# RHD2132_headstage1.net
KiCad netlist of a schematic drawn in Altium Designer
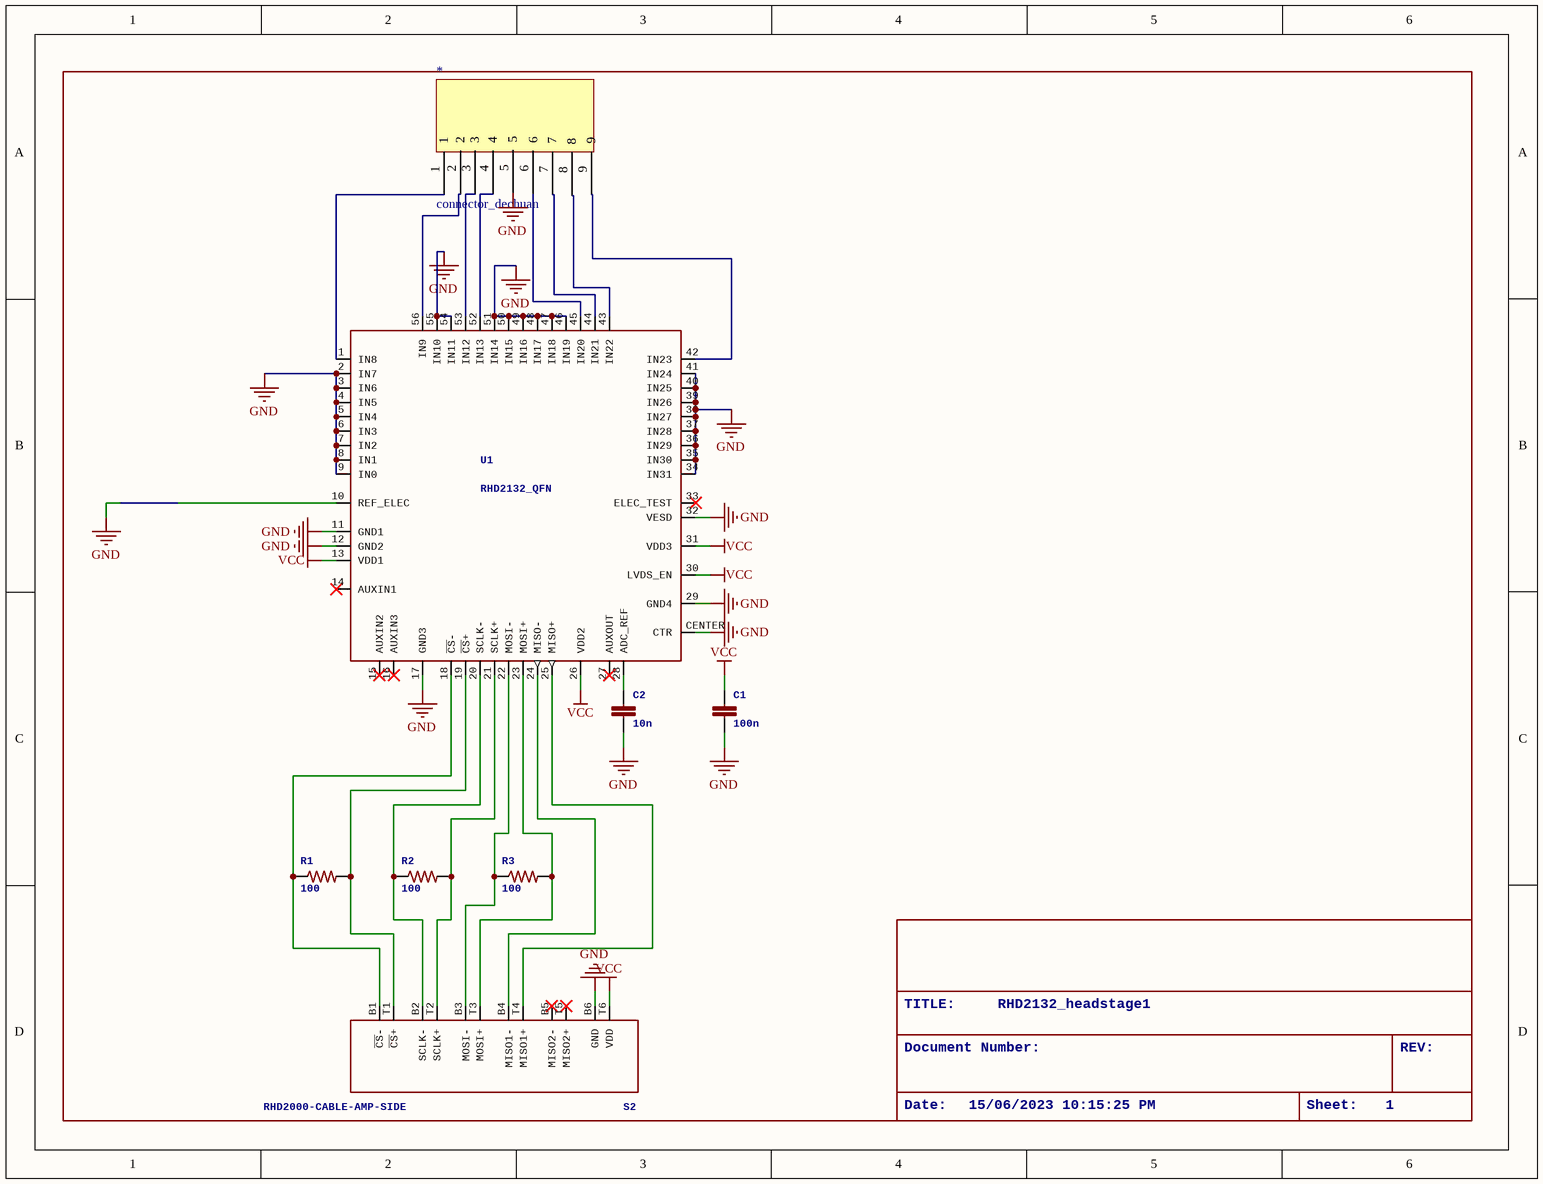
[diagram p0: RHD2132_headstage1.SchDoc]

(export (version "E")
  (design (tool "Eeschema 10.0.6"))
  (components
    (comp (ref "*")
      (value "connector_dechuan")
      (footprint "connector_dechuan")
      (libsource (lib "Schlib1") (part "connector_dechuan"))
    )
    (comp (ref "C1")
      (value "100n")
      (footprint "0402")
      (description "Capacitor")
      (libsource (lib "RHD2000_eval_board") (part "C_0402"))
    )
    (comp (ref "C2")
      (value "10n")
      (footprint "0402")
      (description "Capacitor")
      (libsource (lib "RHD2000_eval_board") (part "C_0402"))
    )
    (comp (ref "R1")
      (value "100")
      (footprint "0402")
      (description "Resistor")
      (libsource (lib "RHD2000_eval_board") (part "R_0402"))
    )
    (comp (ref "R2")
      (value "100")
      (footprint "0402")
      (description "Resistor")
      (libsource (lib "RHD2000_eval_board") (part "R_0402"))
    )
    (comp (ref "R3")
      (value "100")
      (footprint "0402")
      (description "Resistor")
      (libsource (lib "RHD2000_eval_board") (part "R_0402"))
    )
    (comp (ref "S2")
      (value "RHD2000-CABLE-AMP-SIDE")
      (footprint "OMNETICS_PZN-12-AA")
      (libsource (lib "RHD2000") (part "RHD2000-CABLE-AMP-SIDE"))
    )
    (comp (ref "U1")
      (value "RHD2132_QFN")
      (footprint "QFN56_8_X_8_LARGE")
      (libsource (lib "RHD2000") (part "RHD2132_QFN"))
    )
  )
  (nets
    (net (code "1") (name "GND") (class "Default")
      (node (ref "*") (pin "5") (pinfunction "5_5") (pintype "passive"))
      (node (ref "C1") (pin "2") (pinfunction "2_2") (pintype "passive"))
      (node (ref "C2") (pin "2") (pinfunction "2_2") (pintype "passive"))
      (node (ref "S2") (pin "B6") (pinfunction "GND_B6") (pintype "power_in"))
      (node (ref "U1") (pin "10") (pinfunction "REF_ELEC_10") (pintype "passive"))
      (node (ref "U1") (pin "11") (pinfunction "GND1_11") (pintype "power_in"))
      (node (ref "U1") (pin "12") (pinfunction "GND2_12") (pintype "power_in"))
      (node (ref "U1") (pin "17") (pinfunction "GND3_17") (pintype "power_in"))
      (node (ref "U1") (pin "2") (pinfunction "IN7_2") (pintype "passive"))
      (node (ref "U1") (pin "29") (pinfunction "GND4_29") (pintype "power_in"))
      (node (ref "U1") (pin "3") (pinfunction "IN6_3") (pintype "passive"))
      (node (ref "U1") (pin "32") (pinfunction "VESD_32") (pintype "power_in"))
      (node (ref "U1") (pin "34") (pinfunction "IN31_34") (pintype "passive"))
      (node (ref "U1") (pin "35") (pinfunction "IN30_35") (pintype "passive"))
      (node (ref "U1") (pin "36") (pinfunction "IN29_36") (pintype "passive"))
      (node (ref "U1") (pin "37") (pinfunction "IN28_37") (pintype "passive"))
      (node (ref "U1") (pin "38") (pinfunction "IN27_38") (pintype "passive"))
      (node (ref "U1") (pin "39") (pinfunction "IN26_39") (pintype "passive"))
      (node (ref "U1") (pin "4") (pinfunction "IN5_4") (pintype "passive"))
      (node (ref "U1") (pin "40") (pinfunction "IN25_40") (pintype "passive"))
      (node (ref "U1") (pin "41") (pinfunction "IN24_41") (pintype "passive"))
      (node (ref "U1") (pin "46") (pinfunction "IN19_46") (pintype "passive"))
      (node (ref "U1") (pin "47") (pinfunction "IN18_47") (pintype "passive"))
      (node (ref "U1") (pin "48") (pinfunction "IN17_48") (pintype "passive"))
      (node (ref "U1") (pin "49") (pinfunction "IN16_49") (pintype "passive"))
      (node (ref "U1") (pin "5") (pinfunction "IN4_5") (pintype "passive"))
      (node (ref "U1") (pin "50") (pinfunction "IN15_50") (pintype "passive"))
      (node (ref "U1") (pin "51") (pinfunction "IN14_51") (pintype "passive"))
      (node (ref "U1") (pin "54") (pinfunction "IN11_54") (pintype "passive"))
      (node (ref "U1") (pin "55") (pinfunction "IN10_55") (pintype "passive"))
      (node (ref "U1") (pin "6") (pinfunction "IN3_6") (pintype "passive"))
      (node (ref "U1") (pin "7") (pinfunction "IN2_7") (pintype "passive"))
      (node (ref "U1") (pin "8") (pinfunction "IN1_8") (pintype "passive"))
      (node (ref "U1") (pin "9") (pinfunction "IN0_9") (pintype "passive"))
      (node (ref "U1") (pin "CENTER") (pinfunction "CTR_CENTER") (pintype "power_in"))
    )
    (net (code "2") (name "Net-(S2-MISO1+)") (class "Default")
      (node (ref "S2") (pin "T4") (pinfunction "MISO1+_T4") (pintype "passive"))
      (node (ref "U1") (pin "25") (pinfunction "MISO+_25") (pintype "output"))
    )
    (net (code "3") (name "Net-(S2-MISO1-)") (class "Default")
      (node (ref "S2") (pin "B4") (pinfunction "MISO1-_B4") (pintype "passive"))
      (node (ref "U1") (pin "24") (pinfunction "MISO-_24") (pintype "output"))
    )
    (net (code "4") (name "Net-(S2-MOSI+)") (class "Default")
      (node (ref "R3") (pin "2") (pinfunction "2_2") (pintype "passive"))
      (node (ref "S2") (pin "T3") (pinfunction "MOSI+_T3") (pintype "passive"))
      (node (ref "U1") (pin "23") (pinfunction "MOSI+_23") (pintype "passive"))
    )
    (net (code "5") (name "Net-(S2-MOSI-)") (class "Default")
      (node (ref "R3") (pin "1") (pinfunction "1_1") (pintype "passive"))
      (node (ref "S2") (pin "B3") (pinfunction "MOSI-_B3") (pintype "passive"))
      (node (ref "U1") (pin "22") (pinfunction "MOSI-_22") (pintype "passive"))
    )
    (net (code "6") (name "Net-(S2-SCLK+)") (class "Default")
      (node (ref "R2") (pin "2") (pinfunction "2_2") (pintype "passive"))
      (node (ref "S2") (pin "T2") (pinfunction "SCLK+_T2") (pintype "passive"))
      (node (ref "U1") (pin "21") (pinfunction "SCLK+_21") (pintype "passive"))
    )
    (net (code "7") (name "Net-(S2-SCLK-)") (class "Default")
      (node (ref "R2") (pin "1") (pinfunction "1_1") (pintype "passive"))
      (node (ref "S2") (pin "B2") (pinfunction "SCLK-_B2") (pintype "passive"))
      (node (ref "U1") (pin "20") (pinfunction "SCLK-_20") (pintype "passive"))
    )
    (net (code "8") (name "Net-(S2-~{CS}+)") (class "Default")
      (node (ref "R1") (pin "2") (pinfunction "2_2") (pintype "passive"))
      (node (ref "S2") (pin "T1") (pinfunction "~{CS}+_T1") (pintype "passive"))
      (node (ref "U1") (pin "19") (pinfunction "~{CS}+_19") (pintype "passive"))
    )
    (net (code "9") (name "Net-(S2-~{CS}-)") (class "Default")
      (node (ref "R1") (pin "1") (pinfunction "1_1") (pintype "passive"))
      (node (ref "S2") (pin "B1") (pinfunction "~{CS}-_B1") (pintype "passive"))
      (node (ref "U1") (pin "18") (pinfunction "~{CS}-_18") (pintype "passive"))
    )
    (net (code "10") (name "Net-(U1-ADC_REF)") (class "Default")
      (node (ref "C2") (pin "1") (pinfunction "1_1") (pintype "passive"))
      (node (ref "U1") (pin "28") (pinfunction "ADC_REF_28") (pintype "passive"))
    )
    (net (code "11") (name "Net-(U1-IN8)") (class "Default")
      (node (ref "*") (pin "1") (pinfunction "1_1") (pintype "passive"))
      (node (ref "U1") (pin "1") (pinfunction "IN8_1") (pintype "passive"))
    )
    (net (code "12") (name "Net-(U1-IN9)") (class "Default")
      (node (ref "*") (pin "2") (pinfunction "2_2") (pintype "passive"))
      (node (ref "U1") (pin "56") (pinfunction "IN9_56") (pintype "passive"))
    )
    (net (code "13") (name "Net-(U1-IN12)") (class "Default")
      (node (ref "*") (pin "3") (pinfunction "3_3") (pintype "passive"))
      (node (ref "U1") (pin "53") (pinfunction "IN12_53") (pintype "passive"))
    )
    (net (code "14") (name "Net-(U1-IN13)") (class "Default")
      (node (ref "*") (pin "4") (pinfunction "4_4") (pintype "passive"))
      (node (ref "U1") (pin "52") (pinfunction "IN13_52") (pintype "passive"))
    )
    (net (code "15") (name "Net-(U1-IN20)") (class "Default")
      (node (ref "*") (pin "6") (pinfunction "6_6") (pintype "passive"))
      (node (ref "U1") (pin "45") (pinfunction "IN20_45") (pintype "passive"))
    )
    (net (code "16") (name "Net-(U1-IN21)") (class "Default")
      (node (ref "*") (pin "7") (pinfunction "7_7") (pintype "passive"))
      (node (ref "U1") (pin "44") (pinfunction "IN21_44") (pintype "passive"))
    )
    (net (code "17") (name "Net-(U1-IN22)") (class "Default")
      (node (ref "*") (pin "8") (pinfunction "8_8") (pintype "passive"))
      (node (ref "U1") (pin "43") (pinfunction "IN22_43") (pintype "passive"))
    )
    (net (code "18") (name "Net-(U1-IN23)") (class "Default")
      (node (ref "*") (pin "9") (pinfunction "9_9") (pintype "passive"))
      (node (ref "U1") (pin "42") (pinfunction "IN23_42") (pintype "passive"))
    )
    (net (code "19") (name "VCC") (class "Default")
      (node (ref "C1") (pin "1") (pinfunction "1_1") (pintype "passive"))
      (node (ref "S2") (pin "T6") (pinfunction "VDD_T6") (pintype "passive"))
      (node (ref "U1") (pin "13") (pinfunction "VDD1_13") (pintype "power_in"))
      (node (ref "U1") (pin "26") (pinfunction "VDD2_26") (pintype "power_in"))
      (node (ref "U1") (pin "30") (pinfunction "LVDS_EN_30") (pintype "passive"))
      (node (ref "U1") (pin "31") (pinfunction "VDD3_31") (pintype "power_in"))
    )
    (net (code "20") (name "unconnected-(S2-MISO2+-PadT5)") (class "Default")
      (node (ref "S2") (pin "T5") (pinfunction "MISO2+_T5") (pintype "passive+no_connect"))
    )
    (net (code "21") (name "unconnected-(S2-MISO2--PadB5)") (class "Default")
      (node (ref "S2") (pin "B5") (pinfunction "MISO2-_B5") (pintype "passive+no_connect"))
    )
    (net (code "22") (name "unconnected-(U1-AUXIN1-Pad14)") (class "Default")
      (node (ref "U1") (pin "14") (pinfunction "AUXIN1_14") (pintype "passive+no_connect"))
    )
    (net (code "23") (name "unconnected-(U1-AUXIN2-Pad15)") (class "Default")
      (node (ref "U1") (pin "15") (pinfunction "AUXIN2_15") (pintype "passive+no_connect"))
    )
    (net (code "24") (name "unconnected-(U1-AUXIN3-Pad16)") (class "Default")
      (node (ref "U1") (pin "16") (pinfunction "AUXIN3_16") (pintype "passive+no_connect"))
    )
    (net (code "25") (name "unconnected-(U1-AUXOUT-Pad27)") (class "Default")
      (node (ref "U1") (pin "27") (pinfunction "AUXOUT_27") (pintype "tri_state+no_connect"))
    )
    (net (code "26") (name "unconnected-(U1-ELEC_TEST-Pad33)") (class "Default")
      (node (ref "U1") (pin "33") (pinfunction "ELEC_TEST_33") (pintype "passive+no_connect"))
    )
  )
)
